# SCH_Arduboi_2023-01-19.net
KiCad netlist of a schematic drawn in EasyEDA
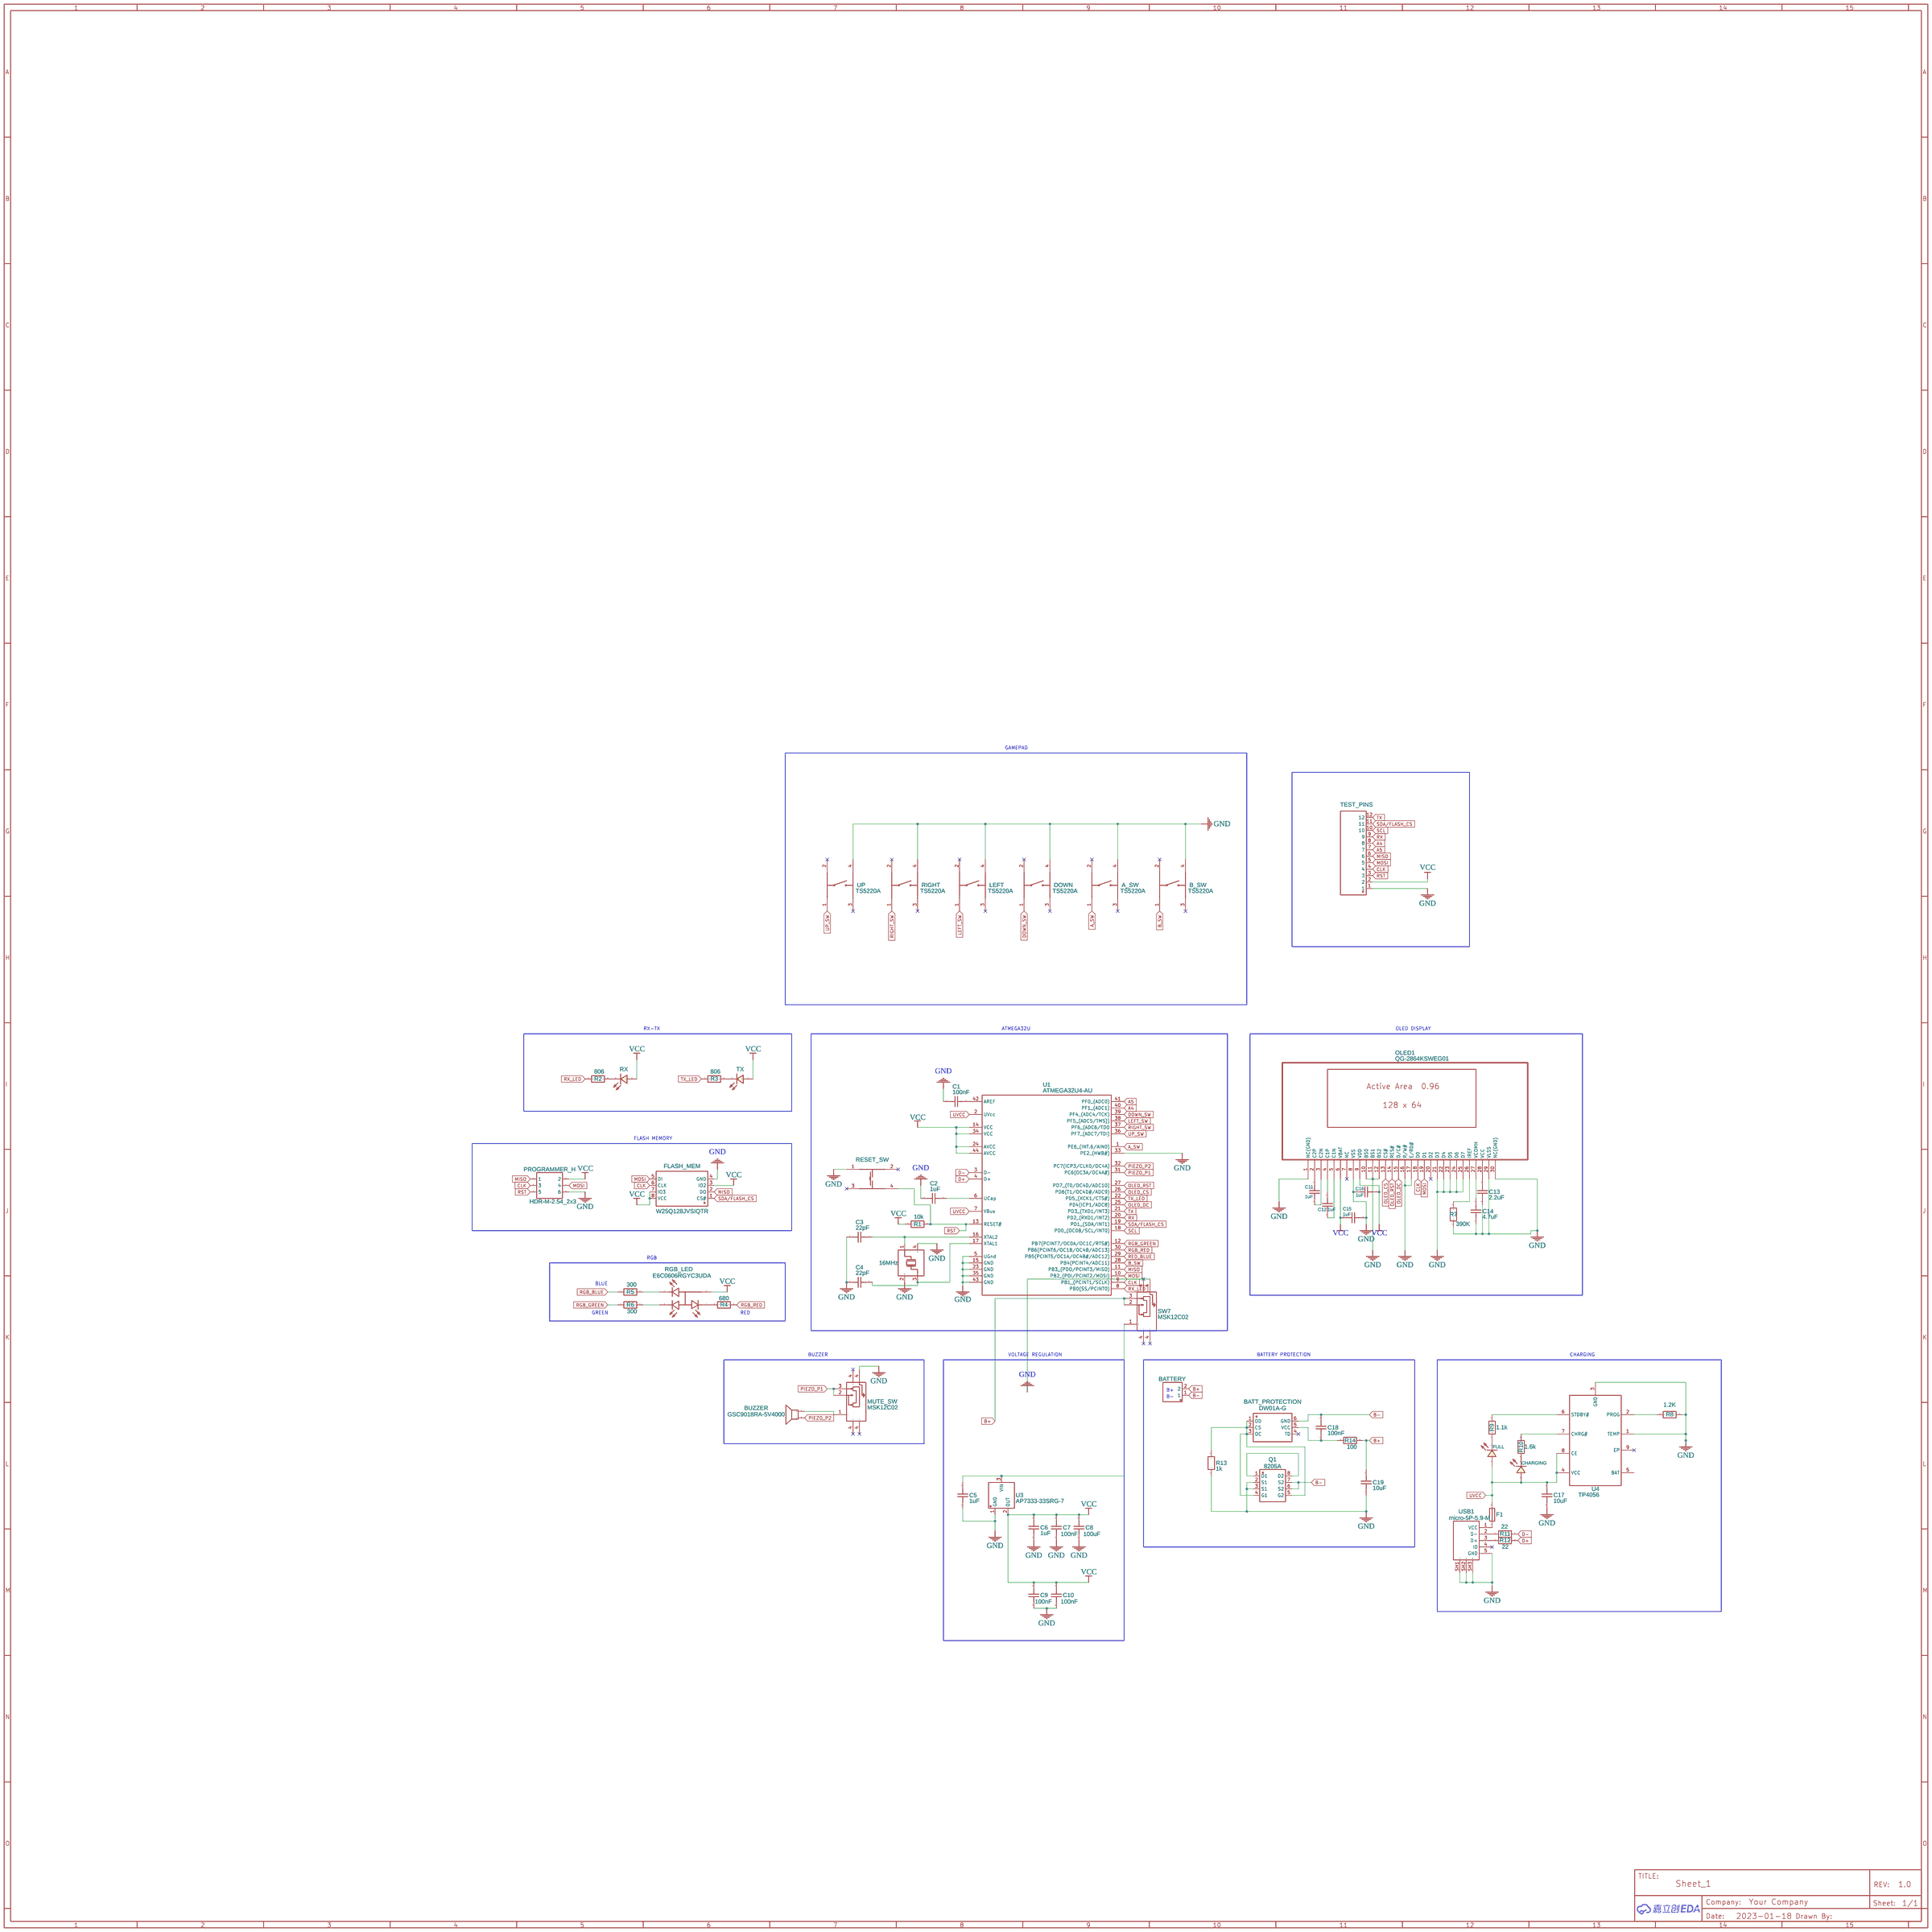
[diagram p0: schematic sheet]

(export (version "E")
  (design (tool "Eeschema 10.0.6"))
  (components
    (comp (ref "A_SW")
      (value "TS5220A")
      (fields (field (name "BOM_Supplier Part") "C412370"))
      (libsource (lib "") (part "TS5220A_3"))
    )
    (comp (ref "BATTERY")
      (value "MTP125-1102S1")
      (fields (field (name "BOM_Supplier Part") "C358684"))
      (libsource (lib "") (part "MTP125-1102S1"))
    )
    (comp (ref "BATT_PROTECTION")
      (value "DW01A-G")
      (fields (field (name "BOM_Supplier Part") "C61503"))
      (libsource (lib "") (part "DW01A-G"))
    )
    (comp (ref "BUZZER")
      (value "GSC9018RA-5V4000")
      (fields (field (name "BOM_Supplier Part") "C255319"))
      (libsource (lib "") (part "GSC9018RA-5V4000"))
    )
    (comp (ref "B_SW")
      (value "TS5220A")
      (fields (field (name "BOM_Supplier Part") "C412370"))
      (libsource (lib "") (part "TS5220A_2"))
    )
    (comp (ref "C1") (value "100nF") (libsource (lib "") (part "C_0603_US_1")))
    (comp (ref "C2") (value "1uF") (libsource (lib "") (part "C_0603_US_1")))
    (comp (ref "C3") (value "22pF") (libsource (lib "") (part "C_0603_US_1")))
    (comp (ref "C4") (value "22pF") (libsource (lib "") (part "C_0603_US_1")))
    (comp (ref "C5") (value "1uF") (libsource (lib "") (part "C_0603_US")))
    (comp (ref "C6") (value "1uF") (libsource (lib "") (part "C_0603_US")))
    (comp (ref "C7") (value "100nF") (libsource (lib "") (part "C_0603_US")))
    (comp (ref "C8") (value "100uF") (libsource (lib "") (part "C_0603_US")))
    (comp (ref "C9") (value "100nF") (libsource (lib "") (part "C_0603_US")))
    (comp (ref "C10") (value "100nF") (libsource (lib "") (part "C_0603_US")))
    (comp (ref "C11") (value "1uF") (libsource (lib "") (part "C_0603_US")))
    (comp (ref "C12") (value "1uF") (libsource (lib "") (part "C_0603_US")))
    (comp (ref "C13") (value "2.2uF") (libsource (lib "") (part "C_0603_US")))
    (comp (ref "C14") (value "4.7uF") (libsource (lib "") (part "C_0603_US")))
    (comp (ref "C15") (value "1uF") (libsource (lib "") (part "C_0603_US_1")))
    (comp (ref "C16") (value "1uF") (libsource (lib "") (part "C_0603_US_1")))
    (comp (ref "C17") (value "10uF") (libsource (lib "") (part "C_0603_US")))
    (comp (ref "C18") (value "100nF") (libsource (lib "") (part "C_0603_US")))
    (comp (ref "C19") (value "10uF") (libsource (lib "") (part "C_0603_US")))
    (comp (ref "CHARGING")
      (value "LED-0603_R")
      (fields
        (field (name "BOM_Manufacturer Part") "19-217/R6C-AL1M2VY/3T")
        (field (name "BOM_Supplier Part") "C72044")
      )
      (libsource (lib "") (part "LED-0603_R"))
    )
    (comp (ref "DOWN")
      (value "TS5220A")
      (fields (field (name "BOM_Supplier Part") "C412370"))
      (libsource (lib "") (part "TS5220A"))
    )
    (comp (ref "F1")
      (value "0805L110SLYR")
      (fields (field (name "BOM_Supplier Part") "C207024"))
      (libsource (lib "") (part "0805L110SLYR"))
    )
    (comp (ref "FLASH_MEM")
      (value "W25Q128JVSIQTR")
      (fields
        (field (name "BOM_Manufacturer Part") "W25Q128JVSIQ")
        (field (name "BOM_Supplier Part") "C97521")
      )
      (libsource (lib "") (part "W25Q128JVSIQTR"))
    )
    (comp (ref "FULL")
      (value "LED-0603_G")
      (fields
        (field (name "BOM_Manufacturer Part") "19-217/GHC-YR1S2/3T")
        (field (name "BOM_Supplier Part") "C72043")
      )
      (libsource (lib "") (part "LED-0603_G"))
    )
    (comp (ref "LEFT")
      (value "TS5220A")
      (fields (field (name "BOM_Supplier Part") "C412370"))
      (libsource (lib "") (part "TS5220A_4"))
    )
    (comp (ref "MUTE_SW")
      (value "MSK12C02")
      (fields (field (name "BOM_Supplier Part") "C431540"))
      (libsource (lib "") (part "MSK12C02"))
    )
    (comp (ref "OLED1")
      (value "QG-2864KSWEG01")
      (fields (field (name "BOM_Supplier Part") "C85007"))
      (libsource (lib "") (part "QG-2864KSWEG01"))
    )
    (comp (ref "PROGRAMMER_H")
      (value "HDR-M-2.54_2x3")
      (fields (field (name "BOM_Supplier Part") "C65114"))
      (libsource (lib "") (part "HDR-M-2.54_2x3"))
    )
    (comp (ref "Q1")
      (value "8205A")
      (fields (field (name "BOM_Supplier Part") "C181100"))
      (libsource (lib "") (part "8205A"))
    )
    (comp (ref "R1") (value "10k") (libsource (lib "") (part "R_0603_EU")))
    (comp (ref "R2") (value "806") (libsource (lib "") (part "R_0603_EU")))
    (comp (ref "R3") (value "806") (libsource (lib "") (part "R_0603_EU")))
    (comp (ref "R4") (value "680") (libsource (lib "") (part "R_0603_EU")))
    (comp (ref "R5") (value "300") (libsource (lib "") (part "R_0603_EU")))
    (comp (ref "R6") (value "300") (libsource (lib "") (part "R_0603_EU")))
    (comp (ref "R7") (value "390K") (libsource (lib "") (part "R_0603_EU_1")))
    (comp (ref "R8") (value "1.2K") (libsource (lib "") (part "R_0603_EU")))
    (comp (ref "R9") (value "1.1k") (libsource (lib "") (part "R_0603_EU_1")))
    (comp (ref "R10") (value "1.6k") (libsource (lib "") (part "R_0603_EU_1")))
    (comp (ref "R11") (value "22") (libsource (lib "") (part "R_0603_EU")))
    (comp (ref "R12") (value "22") (libsource (lib "") (part "R_0603_EU")))
    (comp (ref "R13") (value "1k") (libsource (lib "") (part "R_0603_EU_1")))
    (comp (ref "R14") (value "100") (libsource (lib "") (part "R_0603_EU")))
    (comp (ref "RESET_SW")
      (value "K2-1808UN-A4SW-04")
      (fields (field (name "BOM_Supplier Part") "C145878"))
      (libsource (lib "") (part "K2-1808UN-A4SW-04"))
    )
    (comp (ref "RGB_LED")
      (value "E6C0606RGYC3UDA")
      (fields (field (name "BOM_Supplier Part") "C5162234"))
      (libsource (lib "") (part "E6C0606RGYC3UDA"))
    )
    (comp (ref "RIGHT")
      (value "TS5220A")
      (fields (field (name "BOM_Supplier Part") "C412370"))
      (libsource (lib "") (part "TS5220A_1"))
    )
    (comp (ref "RX")
      (value "LED-0603_B")
      (fields
        (field (name "BOM_Manufacturer Part") "19-217/BHC-ZL1M2RY/3T")
        (field (name "BOM_Supplier Part") "C72041")
      )
      (libsource (lib "") (part "LED-0603_B_1"))
    )
    (comp (ref "SW7")
      (value "MSK12C02")
      (fields (field (name "BOM_Supplier Part") "C431540"))
      (libsource (lib "") (part "MSK12C02_1"))
    )
    (comp (ref "TEST_PINS")
      (value "A2541WR-12P")
      (fields (field (name "BOM_Supplier Part") "C225498"))
      (libsource (lib "") (part "A2541WR-12P"))
    )
    (comp (ref "TX")
      (value "LED-0603_B")
      (fields
        (field (name "BOM_Manufacturer Part") "19-217/BHC-ZL1M2RY/3T")
        (field (name "BOM_Supplier Part") "C72041")
      )
      (libsource (lib "") (part "LED-0603_B"))
    )
    (comp (ref "U1")
      (value "ATMEGA32U4-AU")
      (fields (field (name "BOM_Supplier Part") "C44854"))
      (libsource (lib "") (part "ATMEGA32U4-AU"))
    )
    (comp (ref "U2")
      (value "16MHz")
      (fields
        (field (name "BOM_Manufacturer Part") "NX2520SA-16MHZ-STD-CSW-4")
        (field (name "BOM_Supplier Part") "C1985890")
      )
      (libsource (lib "") (part "NX2520SA-16MHZ-STD-CSW-4"))
    )
    (comp (ref "U3")
      (value "AP7333-33SRG-7")
      (fields (field (name "BOM_Supplier Part") "C150745"))
      (libsource (lib "") (part "AP7333-33SRG-7"))
    )
    (comp (ref "U4")
      (value "TP4056")
      (fields
        (field (name "BOM_Manufacturer Part") "TP4056-42-ESOP8")
        (field (name "BOM_Supplier Part") "C16581")
      )
      (libsource (lib "") (part "TP4056"))
    )
    (comp (ref "UP")
      (value "TS5220A")
      (fields (field (name "BOM_Supplier Part") "C412370"))
      (libsource (lib "") (part "TS5220A_5"))
    )
    (comp (ref "USB1")
      (value "micro-5P-5.9-M")
      (fields
        (field (name "BOM_Manufacturer Part") "920-C62A2021S10100")
        (field (name "BOM_Supplier Part") "C40939")
      )
      (libsource (lib "") (part "micro-5P-5.9-M"))
    )
  )
  (nets
    (net (code "1") (name "A4") (class "Default")
      (node (ref "TEST_PINS") (pin "8") (pinfunction "8_8") (pintype "unspecified"))
      (node (ref "U1") (pin "40") (pinfunction "PF1_(ADC1)_40") (pintype "bidirectional"))
    )
    (net (code "2") (name "A5") (class "Default")
      (node (ref "TEST_PINS") (pin "7") (pinfunction "7_7") (pintype "unspecified"))
      (node (ref "U1") (pin "41") (pinfunction "PF0_(ADC0)_41") (pintype "bidirectional"))
    )
    (net (code "3") (name "A_SW") (class "Default")
      (node (ref "A_SW") (pin "1") (pinfunction "1_1") (pintype "unspecified"))
      (node (ref "U1") (pin "1") (pinfunction "PE6_(INT.6/AIN0)_1") (pintype "bidirectional"))
    )
    (net (code "4") (name "B+") (class "Default")
      (node (ref "BATTERY") (pin "2") (pinfunction "2_2") (pintype "unspecified"))
      (node (ref "C19") (pin "2") (pinfunction "2_2") (pintype "unspecified"))
      (node (ref "R14") (pin "2") (pinfunction "2_2") (pintype "unspecified"))
      (node (ref "SW7") (pin "2") (pinfunction "2_2") (pintype "unspecified"))
      (node (ref "SW7") (pin "3") (pinfunction "3_3") (pintype "unspecified"))
    )
    (net (code "5") (name "B-") (class "Default")
      (node (ref "BATTERY") (pin "1") (pinfunction "1_1") (pintype "unspecified"))
      (node (ref "BATT_PROTECTION") (pin "6") (pinfunction "GND_6") (pintype "unspecified"))
      (node (ref "C18") (pin "2") (pinfunction "2_2") (pintype "unspecified"))
      (node (ref "Q1") (pin "6") (pinfunction "S2_6") (pintype "unspecified"))
      (node (ref "Q1") (pin "7") (pinfunction "S2_7") (pintype "unspecified"))
    )
    (net (code "6") (name "B_SW") (class "Default")
      (node (ref "B_SW") (pin "1") (pinfunction "1_1") (pintype "unspecified"))
      (node (ref "U1") (pin "28") (pinfunction "PB4(PCINT4/ADC11)_28") (pintype "bidirectional"))
    )
    (net (code "7") (name "CLK") (class "Default")
      (node (ref "FLASH_MEM") (pin "6") (pinfunction "CLK_6") (pintype "unspecified"))
      (node (ref "OLED1") (pin "18") (pinfunction "D0_18") (pintype "passive"))
      (node (ref "PROGRAMMER_H") (pin "3") (pinfunction "3_3") (pintype "input"))
      (node (ref "TEST_PINS") (pin "4") (pinfunction "4_4") (pintype "unspecified"))
      (node (ref "U1") (pin "9") (pinfunction "PB1_(PCINT1/SCLK)_9") (pintype "bidirectional"))
    )
    (net (code "8") (name "D+") (class "Default")
      (node (ref "R12") (pin "2") (pinfunction "2_2") (pintype "unspecified"))
      (node (ref "U1") (pin "4") (pinfunction "D+_4") (pintype "bidirectional"))
    )
    (net (code "9") (name "D-") (class "Default")
      (node (ref "R11") (pin "2") (pinfunction "2_2") (pintype "unspecified"))
      (node (ref "U1") (pin "3") (pinfunction "D-_3") (pintype "bidirectional"))
    )
    (net (code "10") (name "DOWN_SW") (class "Default")
      (node (ref "DOWN") (pin "1") (pinfunction "1_1") (pintype "unspecified"))
      (node (ref "U1") (pin "39") (pinfunction "PF4_(ADC4/TCK)_39") (pintype "bidirectional"))
    )
    (net (code "11") (name "GND") (class "Default")
      (node (ref "A_SW") (pin "4") (pinfunction "4_4") (pintype "unspecified"))
      (node (ref "B_SW") (pin "4") (pinfunction "4_4") (pintype "unspecified"))
      (node (ref "C1") (pin "1") (pinfunction "1_1") (pintype "unspecified"))
      (node (ref "C10") (pin "1") (pinfunction "1_1") (pintype "unspecified"))
      (node (ref "C13") (pin "1") (pinfunction "1_1") (pintype "unspecified"))
      (node (ref "C14") (pin "1") (pinfunction "1_1") (pintype "unspecified"))
      (node (ref "C15") (pin "2") (pinfunction "2_2") (pintype "unspecified"))
      (node (ref "C16") (pin "1") (pinfunction "1_1") (pintype "unspecified"))
      (node (ref "C17") (pin "1") (pinfunction "1_1") (pintype "unspecified"))
      (node (ref "C19") (pin "1") (pinfunction "1_1") (pintype "unspecified"))
      (node (ref "C2") (pin "1") (pinfunction "1_1") (pintype "unspecified"))
      (node (ref "C3") (pin "1") (pinfunction "1_1") (pintype "unspecified"))
      (node (ref "C4") (pin "1") (pinfunction "1_1") (pintype "unspecified"))
      (node (ref "C5") (pin "1") (pinfunction "1_1") (pintype "unspecified"))
      (node (ref "C6") (pin "1") (pinfunction "1_1") (pintype "unspecified"))
      (node (ref "C7") (pin "1") (pinfunction "1_1") (pintype "unspecified"))
      (node (ref "C8") (pin "1") (pinfunction "1_1") (pintype "unspecified"))
      (node (ref "C9") (pin "1") (pinfunction "1_1") (pintype "unspecified"))
      (node (ref "DOWN") (pin "4") (pinfunction "4_4") (pintype "unspecified"))
      (node (ref "FLASH_MEM") (pin "4") (pinfunction "GND_4") (pintype "unspecified"))
      (node (ref "LEFT") (pin "4") (pinfunction "4_4") (pintype "unspecified"))
      (node (ref "MUTE_SW") (pin "4") (pinfunction "4_4") (pintype "unspecified"))
      (node (ref "OLED1") (pin "1") (pinfunction "NC(GND)_1") (pintype "passive"))
      (node (ref "OLED1") (pin "10") (pinfunction "BS0_10") (pintype "passive"))
      (node (ref "OLED1") (pin "11") (pinfunction "BS1_11") (pintype "passive"))
      (node (ref "OLED1") (pin "12") (pinfunction "BS2_12") (pintype "passive"))
      (node (ref "OLED1") (pin "16") (pinfunction "R/W#_16") (pintype "passive"))
      (node (ref "OLED1") (pin "17") (pinfunction "E/RD#_17") (pintype "passive"))
      (node (ref "OLED1") (pin "21") (pinfunction "D3_21") (pintype "passive"))
      (node (ref "OLED1") (pin "22") (pinfunction "D4_22") (pintype "passive"))
      (node (ref "OLED1") (pin "23") (pinfunction "D5_23") (pintype "passive"))
      (node (ref "OLED1") (pin "24") (pinfunction "D6_24") (pintype "passive"))
      (node (ref "OLED1") (pin "25") (pinfunction "D7_25") (pintype "passive"))
      (node (ref "OLED1") (pin "29") (pinfunction "VLSS_29") (pintype "passive"))
      (node (ref "OLED1") (pin "30") (pinfunction "NC(GND)_30") (pintype "passive"))
      (node (ref "OLED1") (pin "8") (pinfunction "VSS_8") (pintype "passive"))
      (node (ref "PROGRAMMER_H") (pin "6") (pinfunction "6_6") (pintype "input"))
      (node (ref "Q1") (pin "2") (pinfunction "S1_2") (pintype "unspecified"))
      (node (ref "Q1") (pin "3") (pinfunction "S1_3") (pintype "unspecified"))
      (node (ref "R13") (pin "1") (pinfunction "1_1") (pintype "unspecified"))
      (node (ref "R7") (pin "1") (pinfunction "1_1") (pintype "unspecified"))
      (node (ref "R8") (pin "2") (pinfunction "2_2") (pintype "unspecified"))
      (node (ref "RESET_SW") (pin "1") (pinfunction "1_1") (pintype "unspecified"))
      (node (ref "RIGHT") (pin "4") (pinfunction "4_4") (pintype "unspecified"))
      (node (ref "SW7") (pin "4") (pinfunction "4_4") (pintype "unspecified"))
      (node (ref "TEST_PINS") (pin "1") (pinfunction "1_1") (pintype "unspecified"))
      (node (ref "U1") (pin "15") (pinfunction "GND_15") (pintype "passive"))
      (node (ref "U1") (pin "23") (pinfunction "GND_23") (pintype "passive"))
      (node (ref "U1") (pin "33") (pinfunction "PE2_(HWB#)_33") (pintype "bidirectional"))
      (node (ref "U1") (pin "35") (pinfunction "GND_35") (pintype "passive"))
      (node (ref "U1") (pin "43") (pinfunction "GND_43") (pintype "passive"))
      (node (ref "U1") (pin "5") (pinfunction "UGnd_5") (pintype "passive"))
      (node (ref "U2") (pin "2") (pinfunction "GND_2") (pintype "unspecified"))
      (node (ref "U2") (pin "4") (pinfunction "GND_4") (pintype "unspecified"))
      (node (ref "U3") (pin "1") (pinfunction "GND_1") (pintype "unspecified"))
      (node (ref "U4") (pin "1") (pinfunction "TEMP_1") (pintype "unspecified"))
      (node (ref "U4") (pin "3") (pinfunction "GND_3") (pintype "unspecified"))
      (node (ref "UP") (pin "4") (pinfunction "4_4") (pintype "unspecified"))
      (node (ref "USB1") (pin "5") (pinfunction "GND_5") (pintype "input"))
      (node (ref "USB1") (pin "SH1") (pinfunction "SH1_SH1") (pintype "input"))
      (node (ref "USB1") (pin "SH2") (pinfunction "SH2_SH2") (pintype "input"))
      (node (ref "USB1") (pin "SH3") (pinfunction "SH3_SH3") (pintype "input"))
    )
    (net (code "12") (name "LEFT_SW") (class "Default")
      (node (ref "LEFT") (pin "1") (pinfunction "1_1") (pintype "unspecified"))
      (node (ref "U1") (pin "38") (pinfunction "PF5_(ADC5/TMS))_38") (pintype "bidirectional"))
    )
    (net (code "13") (name "MISO") (class "Default")
      (node (ref "FLASH_MEM") (pin "2") (pinfunction "DO_2") (pintype "unspecified"))
      (node (ref "PROGRAMMER_H") (pin "1") (pinfunction "1_1") (pintype "input"))
      (node (ref "TEST_PINS") (pin "6") (pinfunction "6_6") (pintype "unspecified"))
      (node (ref "U1") (pin "11") (pinfunction "PB3_(PDO/PCINT3/MISO)_11") (pintype "bidirectional"))
    )
    (net (code "14") (name "MOSI") (class "Default")
      (node (ref "FLASH_MEM") (pin "5") (pinfunction "DI_5") (pintype "unspecified"))
      (node (ref "OLED1") (pin "19") (pinfunction "D1_19") (pintype "passive"))
      (node (ref "PROGRAMMER_H") (pin "4") (pinfunction "4_4") (pintype "input"))
      (node (ref "TEST_PINS") (pin "5") (pinfunction "5_5") (pintype "unspecified"))
      (node (ref "U1") (pin "10") (pinfunction "PB2_(PDI/PCINT2/MOSI)_10") (pintype "bidirectional"))
    )
    (net (code "15") (name "Net-(BATT_PROTECTION-CS)") (class "Default")
      (node (ref "BATT_PROTECTION") (pin "1") (pinfunction "OD_1") (pintype "unspecified"))
      (node (ref "BATT_PROTECTION") (pin "2") (pinfunction "CS_2") (pintype "unspecified"))
      (node (ref "BATT_PROTECTION") (pin "3") (pinfunction "OC_3") (pintype "unspecified"))
      (node (ref "Q1") (pin "4") (pinfunction "G1_4") (pintype "unspecified"))
      (node (ref "Q1") (pin "5") (pinfunction "G2_5") (pintype "unspecified"))
      (node (ref "R13") (pin "2") (pinfunction "2_2") (pintype "unspecified"))
    )
    (net (code "16") (name "Net-(BATT_PROTECTION-VCC)") (class "Default")
      (node (ref "BATT_PROTECTION") (pin "5") (pinfunction "VCC_5") (pintype "unspecified"))
      (node (ref "C18") (pin "1") (pinfunction "1_1") (pintype "unspecified"))
      (node (ref "R14") (pin "1") (pinfunction "1_1") (pintype "unspecified"))
    )
    (net (code "17") (name "Net-(BUZZER-Pad2)") (class "Default")
      (node (ref "BUZZER") (pin "2") (pinfunction "2_2") (pintype "unspecified"))
      (node (ref "MUTE_SW") (pin "1") (pinfunction "1_1") (pintype "unspecified"))
    )
    (net (code "18") (name "Net-(CHARGING-Pad2)") (class "Default")
      (node (ref "CHARGING") (pin "2") (pinfunction "2_2") (pintype "unspecified"))
      (node (ref "R10") (pin "1") (pinfunction "1_1") (pintype "unspecified"))
    )
    (net (code "19") (name "Net-(FULL-Pad2)") (class "Default")
      (node (ref "FULL") (pin "2") (pinfunction "2_2") (pintype "unspecified"))
      (node (ref "R9") (pin "1") (pinfunction "1_1") (pintype "unspecified"))
    )
    (net (code "20") (name "Net-(OLED1-C1N)") (class "Default")
      (node (ref "C12") (pin "1") (pinfunction "1_1") (pintype "unspecified"))
      (node (ref "OLED1") (pin "5") (pinfunction "C1N_5") (pintype "passive"))
    )
    (net (code "21") (name "Net-(OLED1-C1P)") (class "Default")
      (node (ref "C12") (pin "2") (pinfunction "2_2") (pintype "unspecified"))
      (node (ref "OLED1") (pin "4") (pinfunction "C1P_4") (pintype "passive"))
    )
    (net (code "22") (name "Net-(OLED1-C2N)") (class "Default")
      (node (ref "C11") (pin "1") (pinfunction "1_1") (pintype "unspecified"))
      (node (ref "OLED1") (pin "3") (pinfunction "C2N_3") (pintype "passive"))
    )
    (net (code "23") (name "Net-(OLED1-C2P)") (class "Default")
      (node (ref "C11") (pin "2") (pinfunction "2_2") (pintype "unspecified"))
      (node (ref "OLED1") (pin "2") (pinfunction "C2P_2") (pintype "passive"))
    )
    (net (code "24") (name "Net-(OLED1-IREF)") (class "Default")
      (node (ref "OLED1") (pin "26") (pinfunction "IREF_26") (pintype "passive"))
      (node (ref "R7") (pin "2") (pinfunction "2_2") (pintype "unspecified"))
    )
    (net (code "25") (name "Net-(OLED1-VCC)") (class "Default")
      (node (ref "C13") (pin "2") (pinfunction "2_2") (pintype "unspecified"))
      (node (ref "OLED1") (pin "28") (pinfunction "VCC_28") (pintype "passive"))
    )
    (net (code "26") (name "Net-(OLED1-VCOMH)") (class "Default")
      (node (ref "C14") (pin "2") (pinfunction "2_2") (pintype "unspecified"))
      (node (ref "OLED1") (pin "27") (pinfunction "VCOMH_27") (pintype "passive"))
    )
    (net (code "27") (name "Net-(Q1-D1)") (class "Default")
      (node (ref "Q1") (pin "1") (pinfunction "D1_1") (pintype "unspecified"))
      (node (ref "Q1") (pin "8") (pinfunction "D2_8") (pintype "unspecified"))
    )
    (net (code "28") (name "Net-(R2-Pad2)") (class "Default")
      (node (ref "R2") (pin "2") (pinfunction "2_2") (pintype "unspecified"))
      (node (ref "RX") (pin "2") (pinfunction "2_2") (pintype "unspecified"))
    )
    (net (code "29") (name "Net-(R3-Pad2)") (class "Default")
      (node (ref "R3") (pin "2") (pinfunction "2_2") (pintype "unspecified"))
      (node (ref "TX") (pin "2") (pinfunction "2_2") (pintype "unspecified"))
    )
    (net (code "30") (name "Net-(R4-Pad1)") (class "Default")
      (node (ref "R4") (pin "1") (pinfunction "1_1") (pintype "unspecified"))
      (node (ref "RGB_LED") (pin "4") (pinfunction "-_4") (pintype "unspecified"))
    )
    (net (code "31") (name "Net-(R5-Pad2)") (class "Default")
      (node (ref "R5") (pin "2") (pinfunction "2_2") (pintype "unspecified"))
      (node (ref "RGB_LED") (pin "1") (pinfunction "-_1") (pintype "unspecified"))
    )
    (net (code "32") (name "Net-(R6-Pad2)") (class "Default")
      (node (ref "R6") (pin "2") (pinfunction "2_2") (pintype "unspecified"))
      (node (ref "RGB_LED") (pin "3") (pinfunction "-_3") (pintype "unspecified"))
    )
    (net (code "33") (name "Net-(U1-AREF)") (class "Default")
      (node (ref "C1") (pin "2") (pinfunction "2_2") (pintype "unspecified"))
      (node (ref "U1") (pin "42") (pinfunction "AREF_42") (pintype "unspecified"))
    )
    (net (code "34") (name "Net-(U1-UCap)") (class "Default")
      (node (ref "C2") (pin "2") (pinfunction "2_2") (pintype "unspecified"))
      (node (ref "U1") (pin "6") (pinfunction "UCap_6") (pintype "unspecified"))
    )
    (net (code "35") (name "Net-(U1-XTAL1)") (class "Default")
      (node (ref "C4") (pin "2") (pinfunction "2_2") (pintype "unspecified"))
      (node (ref "U1") (pin "17") (pinfunction "XTAL1_17") (pintype "unspecified"))
      (node (ref "U2") (pin "3") (pinfunction "OSC2_3") (pintype "unspecified"))
    )
    (net (code "36") (name "Net-(U1-XTAL2)") (class "Default")
      (node (ref "C3") (pin "2") (pinfunction "2_2") (pintype "unspecified"))
      (node (ref "U1") (pin "16") (pinfunction "XTAL2_16") (pintype "output"))
      (node (ref "U2") (pin "1") (pinfunction "OSC1_1") (pintype "unspecified"))
    )
    (net (code "37") (name "Net-(U3-VIN)") (class "Default")
      (node (ref "C5") (pin "2") (pinfunction "2_2") (pintype "unspecified"))
      (node (ref "SW7") (pin "1") (pinfunction "1_1") (pintype "unspecified"))
      (node (ref "U3") (pin "3") (pinfunction "VIN_3") (pintype "unspecified"))
    )
    (net (code "38") (name "Net-(U4-CHRG#)") (class "Default")
      (node (ref "R10") (pin "2") (pinfunction "2_2") (pintype "unspecified"))
      (node (ref "U4") (pin "7") (pinfunction "CHRG#_7") (pintype "unspecified"))
    )
    (net (code "39") (name "Net-(U4-PROG)") (class "Default")
      (node (ref "R8") (pin "1") (pinfunction "1_1") (pintype "unspecified"))
      (node (ref "U4") (pin "2") (pinfunction "PROG_2") (pintype "unspecified"))
    )
    (net (code "40") (name "Net-(U4-STDBY#)") (class "Default")
      (node (ref "R9") (pin "2") (pinfunction "2_2") (pintype "unspecified"))
      (node (ref "U4") (pin "6") (pinfunction "STDBY#_6") (pintype "unspecified"))
    )
    (net (code "41") (name "Net-(USB1-D+)") (class "Default")
      (node (ref "R12") (pin "1") (pinfunction "1_1") (pintype "unspecified"))
      (node (ref "USB1") (pin "3") (pinfunction "D+_3") (pintype "input"))
    )
    (net (code "42") (name "Net-(USB1-D-)") (class "Default")
      (node (ref "R11") (pin "1") (pinfunction "1_1") (pintype "unspecified"))
      (node (ref "USB1") (pin "2") (pinfunction "D-_2") (pintype "input"))
    )
    (net (code "43") (name "Net-(USB1-VCC)") (class "Default")
      (node (ref "F1") (pin "1") (pinfunction "1_1") (pintype "unspecified"))
      (node (ref "USB1") (pin "1") (pinfunction "VCC_1") (pintype "input"))
    )
    (net (code "44") (name "OLED_CS") (class "Default")
      (node (ref "OLED1") (pin "13") (pinfunction "CS#_13") (pintype "passive"))
      (node (ref "U1") (pin "26") (pinfunction "PD6(T1/OC4D#/ADC9)_26") (pintype "bidirectional"))
    )
    (net (code "45") (name "OLED_DC") (class "Default")
      (node (ref "OLED1") (pin "15") (pinfunction "D/C#_15") (pintype "passive"))
      (node (ref "U1") (pin "25") (pinfunction "PD4(ICP1/ADC8)_25") (pintype "bidirectional"))
    )
    (net (code "46") (name "OLED_RST") (class "Default")
      (node (ref "OLED1") (pin "14") (pinfunction "RES#_14") (pintype "passive"))
      (node (ref "U1") (pin "27") (pinfunction "PD7_(T0/OC4D/ADC10)_27") (pintype "bidirectional"))
    )
    (net (code "47") (name "PIEZO_P1") (class "Default")
      (node (ref "MUTE_SW") (pin "2") (pinfunction "2_2") (pintype "unspecified"))
      (node (ref "MUTE_SW") (pin "3") (pinfunction "3_3") (pintype "unspecified"))
      (node (ref "U1") (pin "31") (pinfunction "PC6(OC3A/OC4A#)_31") (pintype "bidirectional"))
    )
    (net (code "48") (name "PIEZO_P2") (class "Default")
      (node (ref "BUZZER") (pin "1") (pinfunction "1_1") (pintype "unspecified"))
      (node (ref "U1") (pin "32") (pinfunction "PC7(ICP3/CLK0/OC4A)_32") (pintype "bidirectional"))
    )
    (net (code "49") (name "RED_BLUE") (class "Default")
      (node (ref "U1") (pin "29") (pinfunction "PB5(PCINT5/OC1A/OC4B#/ADC12)_29") (pintype "bidirectional"))
    )
    (net (code "50") (name "RGB_BLUE") (class "Default")
      (node (ref "R5") (pin "1") (pinfunction "1_1") (pintype "unspecified"))
    )
    (net (code "51") (name "RGB_GREEN") (class "Default")
      (node (ref "R6") (pin "1") (pinfunction "1_1") (pintype "unspecified"))
      (node (ref "U1") (pin "12") (pinfunction "PB7(PCINT7/OC0A/OC1C/RTS#)_12") (pintype "bidirectional"))
    )
    (net (code "52") (name "RGB_RED") (class "Default")
      (node (ref "R4") (pin "2") (pinfunction "2_2") (pintype "unspecified"))
      (node (ref "U1") (pin "30") (pinfunction "PB6(PCINT6/OC1B/OC4B/ADC13)_30") (pintype "bidirectional"))
    )
    (net (code "53") (name "RIGHT_SW") (class "Default")
      (node (ref "RIGHT") (pin "1") (pinfunction "1_1") (pintype "unspecified"))
      (node (ref "U1") (pin "37") (pinfunction "PF6_(ADC6/TDO_37") (pintype "bidirectional"))
    )
    (net (code "54") (name "RST") (class "Default")
      (node (ref "PROGRAMMER_H") (pin "5") (pinfunction "5_5") (pintype "input"))
      (node (ref "R1") (pin "2") (pinfunction "2_2") (pintype "unspecified"))
      (node (ref "RESET_SW") (pin "4") (pinfunction "4_4") (pintype "unspecified"))
      (node (ref "TEST_PINS") (pin "3") (pinfunction "3_3") (pintype "unspecified"))
      (node (ref "U1") (pin "13") (pinfunction "RESET#_13") (pintype "unspecified"))
    )
    (net (code "55") (name "RX") (class "Default")
      (node (ref "TEST_PINS") (pin "9") (pinfunction "9_9") (pintype "unspecified"))
      (node (ref "U1") (pin "20") (pinfunction "PD2_(RXD1/INT2)_20") (pintype "bidirectional"))
    )
    (net (code "56") (name "RX_LED") (class "Default")
      (node (ref "R2") (pin "1") (pinfunction "1_1") (pintype "unspecified"))
      (node (ref "U1") (pin "8") (pinfunction "PB0(SS/PCINT0)_8") (pintype "bidirectional"))
    )
    (net (code "57") (name "SCL") (class "Default")
      (node (ref "TEST_PINS") (pin "10") (pinfunction "10_10") (pintype "unspecified"))
      (node (ref "U1") (pin "18") (pinfunction "PD0_(OC0B/SCL/INT0)_18") (pintype "bidirectional"))
    )
    (net (code "58") (name "SDA{slash}FLASH_CS") (class "Default")
      (node (ref "FLASH_MEM") (pin "1") (pinfunction "CS#_1") (pintype "unspecified"))
      (node (ref "TEST_PINS") (pin "11") (pinfunction "11_11") (pintype "unspecified"))
      (node (ref "U1") (pin "19") (pinfunction "PD1_(SDA/INT1)_19") (pintype "bidirectional"))
    )
    (net (code "59") (name "TX") (class "Default")
      (node (ref "TEST_PINS") (pin "12") (pinfunction "12_12") (pintype "unspecified"))
      (node (ref "U1") (pin "21") (pinfunction "PD3_(TXD1/INT3)_21") (pintype "bidirectional"))
    )
    (net (code "60") (name "TX_LED") (class "Default")
      (node (ref "R3") (pin "1") (pinfunction "1_1") (pintype "unspecified"))
      (node (ref "U1") (pin "22") (pinfunction "PD5_(XCK1/CTS#)_22") (pintype "bidirectional"))
    )
    (net (code "61") (name "UP_SW") (class "Default")
      (node (ref "U1") (pin "36") (pinfunction "PF7_(ADC7/TDI)_36") (pintype "bidirectional"))
      (node (ref "UP") (pin "1") (pinfunction "1_1") (pintype "unspecified"))
    )
    (net (code "62") (name "UVCC") (class "Default")
      (node (ref "C17") (pin "2") (pinfunction "2_2") (pintype "unspecified"))
      (node (ref "CHARGING") (pin "1") (pinfunction "1_1") (pintype "unspecified"))
      (node (ref "F1") (pin "2") (pinfunction "2_2") (pintype "unspecified"))
      (node (ref "FULL") (pin "1") (pinfunction "1_1") (pintype "unspecified"))
      (node (ref "U1") (pin "2") (pinfunction "UVcc_2") (pintype "passive"))
      (node (ref "U1") (pin "7") (pinfunction "VBus_7") (pintype "unspecified"))
      (node (ref "U4") (pin "4") (pinfunction "VCC_4") (pintype "unspecified"))
      (node (ref "U4") (pin "8") (pinfunction "CE_8") (pintype "unspecified"))
    )
    (net (code "63") (name "VCC") (class "Default")
      (node (ref "C10") (pin "2") (pinfunction "2_2") (pintype "unspecified"))
      (node (ref "C15") (pin "1") (pinfunction "1_1") (pintype "unspecified"))
      (node (ref "C16") (pin "2") (pinfunction "2_2") (pintype "unspecified"))
      (node (ref "C6") (pin "2") (pinfunction "2_2") (pintype "unspecified"))
      (node (ref "C7") (pin "2") (pinfunction "2_2") (pintype "unspecified"))
      (node (ref "C8") (pin "2") (pinfunction "2_2") (pintype "unspecified"))
      (node (ref "C9") (pin "2") (pinfunction "2_2") (pintype "unspecified"))
      (node (ref "FLASH_MEM") (pin "3") (pinfunction "IO2_3") (pintype "unspecified"))
      (node (ref "FLASH_MEM") (pin "7") (pinfunction "IO3_7") (pintype "unspecified"))
      (node (ref "FLASH_MEM") (pin "8") (pinfunction "VCC_8") (pintype "unspecified"))
      (node (ref "OLED1") (pin "6") (pinfunction "VBAT_6") (pintype "passive"))
      (node (ref "OLED1") (pin "9") (pinfunction "VDD_9") (pintype "passive"))
      (node (ref "PROGRAMMER_H") (pin "2") (pinfunction "2_2") (pintype "input"))
      (node (ref "R1") (pin "1") (pinfunction "1_1") (pintype "unspecified"))
      (node (ref "RGB_LED") (pin "2") (pinfunction "+_2") (pintype "unspecified"))
      (node (ref "RX") (pin "1") (pinfunction "1_1") (pintype "unspecified"))
      (node (ref "TEST_PINS") (pin "2") (pinfunction "2_2") (pintype "unspecified"))
      (node (ref "TX") (pin "1") (pinfunction "1_1") (pintype "unspecified"))
      (node (ref "U1") (pin "14") (pinfunction "VCC_14") (pintype "passive"))
      (node (ref "U1") (pin "24") (pinfunction "AVCC_24") (pintype "passive"))
      (node (ref "U1") (pin "34") (pinfunction "VCC_34") (pintype "passive"))
      (node (ref "U1") (pin "44") (pinfunction "AVCC_44") (pintype "passive"))
      (node (ref "U3") (pin "2") (pinfunction "OUT_2") (pintype "unspecified"))
    )
    (net (code "64") (name "unconnected-(A_SW-Pad2)") (class "Default")
      (node (ref "A_SW") (pin "2") (pinfunction "2_2") (pintype "unspecified+no_connect"))
    )
    (net (code "65") (name "unconnected-(A_SW-Pad3)") (class "Default")
      (node (ref "A_SW") (pin "3") (pinfunction "3_3") (pintype "unspecified+no_connect"))
    )
    (net (code "66") (name "unconnected-(BATT_PROTECTION-TD-Pad4)") (class "Default")
      (node (ref "BATT_PROTECTION") (pin "4") (pinfunction "TD_4") (pintype "unspecified+no_connect"))
    )
    (net (code "67") (name "unconnected-(B_SW-Pad2)") (class "Default")
      (node (ref "B_SW") (pin "2") (pinfunction "2_2") (pintype "unspecified+no_connect"))
    )
    (net (code "68") (name "unconnected-(B_SW-Pad3)") (class "Default")
      (node (ref "B_SW") (pin "3") (pinfunction "3_3") (pintype "unspecified+no_connect"))
    )
    (net (code "69") (name "unconnected-(DOWN-Pad2)") (class "Default")
      (node (ref "DOWN") (pin "2") (pinfunction "2_2") (pintype "unspecified+no_connect"))
    )
    (net (code "70") (name "unconnected-(DOWN-Pad3)") (class "Default")
      (node (ref "DOWN") (pin "3") (pinfunction "3_3") (pintype "unspecified+no_connect"))
    )
    (net (code "71") (name "unconnected-(LEFT-Pad2)") (class "Default")
      (node (ref "LEFT") (pin "2") (pinfunction "2_2") (pintype "unspecified+no_connect"))
    )
    (net (code "72") (name "unconnected-(LEFT-Pad3)") (class "Default")
      (node (ref "LEFT") (pin "3") (pinfunction "3_3") (pintype "unspecified+no_connect"))
    )
    (net (code "73") (name "unconnected-(MUTE_SW-Pad4)") (class "Default")
      (node (ref "MUTE_SW") (pin "4") (pinfunction "4_4") (pintype "unspecified+no_connect"))
    )
    (net (code "74") (name "unconnected-(MUTE_SW-Pad4)_1") (class "Default")
      (node (ref "MUTE_SW") (pin "4") (pinfunction "4_4") (pintype "unspecified+no_connect"))
    )
    (net (code "75") (name "unconnected-(MUTE_SW-Pad4)_2") (class "Default")
      (node (ref "MUTE_SW") (pin "4") (pinfunction "4_4") (pintype "unspecified+no_connect"))
    )
    (net (code "76") (name "unconnected-(OLED1-D2-Pad20)") (class "Default")
      (node (ref "OLED1") (pin "20") (pinfunction "D2_20") (pintype "passive+no_connect"))
    )
    (net (code "77") (name "unconnected-(OLED1-NC-Pad7)") (class "Default")
      (node (ref "OLED1") (pin "7") (pinfunction "NC_7") (pintype "passive+no_connect"))
    )
    (net (code "78") (name "unconnected-(RESET_SW-Pad2)") (class "Default")
      (node (ref "RESET_SW") (pin "2") (pinfunction "2_2") (pintype "unspecified+no_connect"))
    )
    (net (code "79") (name "unconnected-(RESET_SW-Pad3)") (class "Default")
      (node (ref "RESET_SW") (pin "3") (pinfunction "3_3") (pintype "unspecified+no_connect"))
    )
    (net (code "80") (name "unconnected-(RIGHT-Pad2)") (class "Default")
      (node (ref "RIGHT") (pin "2") (pinfunction "2_2") (pintype "unspecified+no_connect"))
    )
    (net (code "81") (name "unconnected-(RIGHT-Pad3)") (class "Default")
      (node (ref "RIGHT") (pin "3") (pinfunction "3_3") (pintype "unspecified+no_connect"))
    )
    (net (code "82") (name "unconnected-(SW7-Pad4)") (class "Default")
      (node (ref "SW7") (pin "4") (pinfunction "4_4") (pintype "unspecified+no_connect"))
    )
    (net (code "83") (name "unconnected-(SW7-Pad4)_1") (class "Default")
      (node (ref "SW7") (pin "4") (pinfunction "4_4") (pintype "unspecified+no_connect"))
    )
    (net (code "84") (name "unconnected-(U4-BAT-Pad5)") (class "Default")
      (node (ref "U4") (pin "5") (pinfunction "BAT_5") (pintype "unspecified"))
    )
    (net (code "85") (name "unconnected-(U4-EP-Pad9)") (class "Default")
      (node (ref "U4") (pin "9") (pinfunction "EP_9") (pintype "unspecified+no_connect"))
    )
    (net (code "86") (name "unconnected-(UP-Pad2)") (class "Default")
      (node (ref "UP") (pin "2") (pinfunction "2_2") (pintype "unspecified+no_connect"))
    )
    (net (code "87") (name "unconnected-(UP-Pad3)") (class "Default")
      (node (ref "UP") (pin "3") (pinfunction "3_3") (pintype "unspecified+no_connect"))
    )
    (net (code "88") (name "unconnected-(USB1-ID-Pad4)") (class "Default")
      (node (ref "USB1") (pin "4") (pinfunction "ID_4") (pintype "input+no_connect"))
    )
  )
)
